# CONTROL.net
KiCad netlist of a schematic drawn in Altium Designer
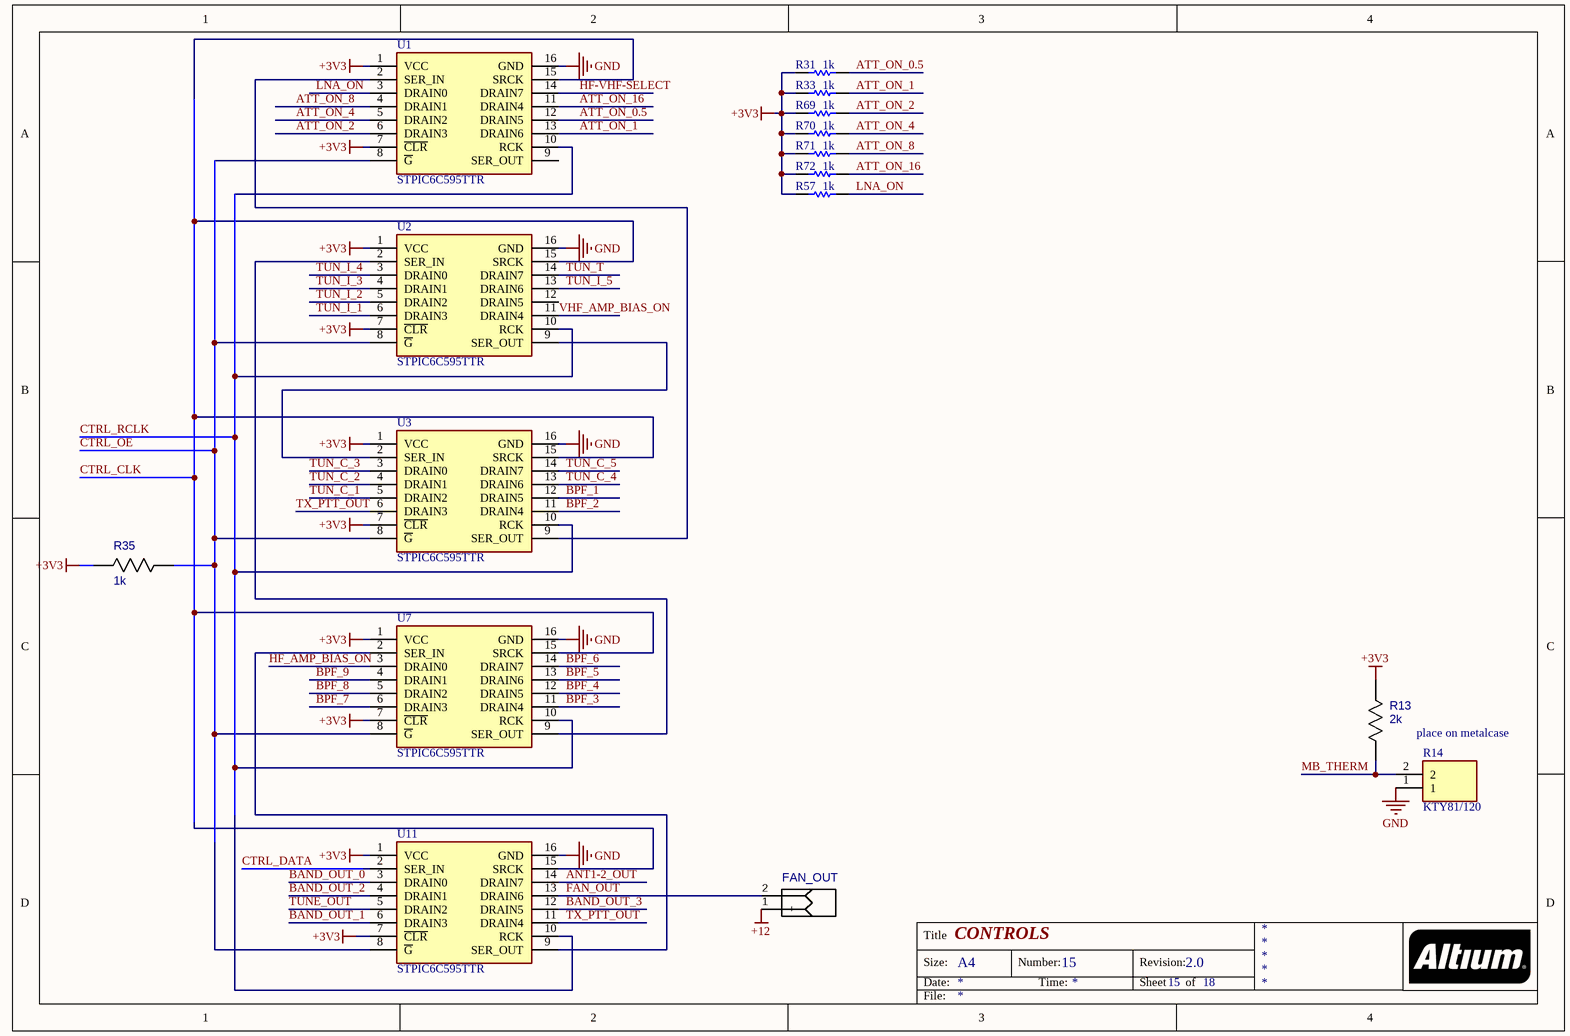
[diagram p0: CONTROL.SchDoc]

(export (version "E")
  (design (tool "Eeschema 10.0.6"))
  (components
    (comp (ref "FAN_OUT")
      (value "51022-0200")
      (footprint "51022-0200")
      (libsource (lib "*") (part "51022-0200"))
    )
    (comp (ref "R13")
      (value "2k")
      (footprint "RES_0805")
      (description "RES_0805")
      (libsource (lib "*") (part "RES_0805"))
    )
    (comp (ref "R14")
      (value "KTY81/120")
      (footprint "TO254P420X460X770-2P")
      (description "Integrated Circuit")
      (fields (field (name "MANUFACTURER_PART_NUMBER") "KTY81/110"))
      (libsource (lib "RF-UNIT-BIG") (part "KTY81_110"))
    )
    (comp (ref "R31")
      (value "1k")
      (footprint "RESC2013X60X40NL20T25")
      (description "RES_0805")
      (fields (field (name "MANUFACTURER") "Panasonic") (field (name "PART NUMBER") "ERA-6AEB303V"))
      (libsource (lib "Altium Content Vault") (part "RES"))
    )
    (comp (ref "R33")
      (value "1k")
      (footprint "RESC2013X60X40NL20T25")
      (description "RES_0805")
      (fields (field (name "MANUFACTURER") "Panasonic") (field (name "PART NUMBER") "ERA-6AEB303V"))
      (libsource (lib "Altium Content Vault") (part "RES"))
    )
    (comp (ref "R35")
      (value "1k")
      (footprint "RES_0805")
      (description "RES_0805")
      (libsource (lib "*") (part "RES_0805"))
    )
    (comp (ref "R57")
      (value "1k")
      (footprint "RESC2013X60X40NL20T25")
      (description "RES_0805")
      (fields (field (name "MANUFACTURER") "Panasonic") (field (name "PART NUMBER") "ERA-6AEB303V"))
      (libsource (lib "Altium Content Vault") (part "RES"))
    )
    (comp (ref "R69")
      (value "1k")
      (footprint "RESC2013X60X40NL20T25")
      (description "RES_0805")
      (fields (field (name "MANUFACTURER") "Panasonic") (field (name "PART NUMBER") "ERA-6AEB303V"))
      (libsource (lib "Altium Content Vault") (part "RES"))
    )
    (comp (ref "R70")
      (value "1k")
      (footprint "RESC2013X60X40NL20T25")
      (description "RES_0805")
      (fields (field (name "MANUFACTURER") "Panasonic") (field (name "PART NUMBER") "ERA-6AEB303V"))
      (libsource (lib "Altium Content Vault") (part "RES"))
    )
    (comp (ref "R71")
      (value "1k")
      (footprint "RESC2013X60X40NL20T25")
      (description "RES_0805")
      (fields (field (name "MANUFACTURER") "Panasonic") (field (name "PART NUMBER") "ERA-6AEB303V"))
      (libsource (lib "Altium Content Vault") (part "RES"))
    )
    (comp (ref "R72")
      (value "1k")
      (footprint "RESC2013X60X40NL20T25")
      (description "RES_0805")
      (fields (field (name "MANUFACTURER") "Panasonic") (field (name "PART NUMBER") "ERA-6AEB303V"))
      (libsource (lib "Altium Content Vault") (part "RES"))
    )
    (comp (ref "U1")
      (value "STPIC6C595TTR")
      (footprint "SamacSys:SOP65P640X120-16N")
      (description "Integrated Circuit")
      (fields (field (name "MOUSER PART NUMBER") "511-STPIC6C595T"))
      (libsource (lib "") (part "STPIC6C595TTR_1"))
    )
    (comp (ref "U2")
      (value "STPIC6C595TTR")
      (footprint "SamacSys:SOP65P640X120-16N")
      (description "Integrated Circuit")
      (fields (field (name "MOUSER PART NUMBER") "511-STPIC6C595T"))
      (libsource (lib "*") (part "STPIC6C595TTR"))
    )
    (comp (ref "U3")
      (value "STPIC6C595TTR")
      (footprint "SamacSys:SOP65P640X120-16N")
      (description "Integrated Circuit")
      (fields (field (name "MOUSER PART NUMBER") "511-STPIC6C595T"))
      (libsource (lib "*") (part "STPIC6C595TTR"))
    )
    (comp (ref "U7")
      (value "STPIC6C595TTR")
      (footprint "SamacSys:SOP65P640X120-16N")
      (description "Integrated Circuit")
      (fields (field (name "MOUSER PART NUMBER") "511-STPIC6C595T"))
      (libsource (lib "*") (part "STPIC6C595TTR"))
    )
    (comp (ref "U11")
      (value "STPIC6C595TTR")
      (footprint "SamacSys:SOP65P640X120-16N")
      (description "Integrated Circuit")
      (fields (field (name "MOUSER PART NUMBER") "511-STPIC6C595T"))
      (libsource (lib "*") (part "STPIC6C595TTR"))
    )
  )
  (nets
    (net (code "1") (name "+3V3") (class "Default")
      (node (ref "R13") (pin "2") (pinfunction "2_2") (pintype "passive"))
      (node (ref "R31") (pin "2") (pinfunction "2_2") (pintype "passive"))
      (node (ref "R33") (pin "2") (pinfunction "2_2") (pintype "passive"))
      (node (ref "R35") (pin "1") (pinfunction "1_1") (pintype "passive"))
      (node (ref "R57") (pin "2") (pinfunction "2_2") (pintype "passive"))
      (node (ref "R69") (pin "2") (pinfunction "2_2") (pintype "passive"))
      (node (ref "R70") (pin "2") (pinfunction "2_2") (pintype "passive"))
      (node (ref "R71") (pin "2") (pinfunction "2_2") (pintype "passive"))
      (node (ref "R72") (pin "2") (pinfunction "2_2") (pintype "passive"))
      (node (ref "U1") (pin "1") (pinfunction "VCC_1") (pintype "passive"))
      (node (ref "U1") (pin "7") (pinfunction "~{CLR}_7") (pintype "passive"))
      (node (ref "U11") (pin "1") (pinfunction "VCC_1") (pintype "passive"))
      (node (ref "U11") (pin "7") (pinfunction "~{CLR}_7") (pintype "passive"))
      (node (ref "U2") (pin "1") (pinfunction "VCC_1") (pintype "passive"))
      (node (ref "U2") (pin "7") (pinfunction "~{CLR}_7") (pintype "passive"))
      (node (ref "U3") (pin "1") (pinfunction "VCC_1") (pintype "passive"))
      (node (ref "U3") (pin "7") (pinfunction "~{CLR}_7") (pintype "passive"))
      (node (ref "U7") (pin "1") (pinfunction "VCC_1") (pintype "passive"))
      (node (ref "U7") (pin "7") (pinfunction "~{CLR}_7") (pintype "passive"))
    )
    (net (code "2") (name "+12") (class "Default")
      (node (ref "FAN_OUT") (pin "1") (pinfunction "+_1") (pintype "passive"))
    )
    (net (code "4") (name "/ANT1-2_OUT") (class "Default")
      (node (ref "U11") (pin "14") (pinfunction "DRAIN7_14") (pintype "passive"))
    )
    (net (code "5") (name "/ATT_ON_0.5") (class "Default")
      (node (ref "R31") (pin "1") (pinfunction "1_1") (pintype "passive"))
      (node (ref "U1") (pin "12") (pinfunction "DRAIN5_12") (pintype "passive"))
    )
    (net (code "6") (name "/ATT_ON_1") (class "Default")
      (node (ref "R33") (pin "1") (pinfunction "1_1") (pintype "passive"))
      (node (ref "U1") (pin "13") (pinfunction "DRAIN6_13") (pintype "passive"))
    )
    (net (code "7") (name "/ATT_ON_2") (class "Default")
      (node (ref "R69") (pin "1") (pinfunction "1_1") (pintype "passive"))
      (node (ref "U1") (pin "6") (pinfunction "DRAIN3_6") (pintype "passive"))
    )
    (net (code "8") (name "/ATT_ON_4") (class "Default")
      (node (ref "R70") (pin "1") (pinfunction "1_1") (pintype "passive"))
      (node (ref "U1") (pin "5") (pinfunction "DRAIN2_5") (pintype "passive"))
    )
    (net (code "9") (name "/ATT_ON_8") (class "Default")
      (node (ref "R71") (pin "1") (pinfunction "1_1") (pintype "passive"))
      (node (ref "U1") (pin "4") (pinfunction "DRAIN1_4") (pintype "passive"))
    )
    (net (code "10") (name "/ATT_ON_16") (class "Default")
      (node (ref "R72") (pin "1") (pinfunction "1_1") (pintype "passive"))
      (node (ref "U1") (pin "11") (pinfunction "DRAIN4_11") (pintype "passive"))
    )
    (net (code "11") (name "/BAND_OUT_0") (class "Default")
      (node (ref "U11") (pin "3") (pinfunction "DRAIN0_3") (pintype "passive"))
    )
    (net (code "12") (name "/BAND_OUT_1") (class "Default")
      (node (ref "U11") (pin "6") (pinfunction "DRAIN3_6") (pintype "passive"))
    )
    (net (code "13") (name "/BAND_OUT_2") (class "Default")
      (node (ref "U11") (pin "4") (pinfunction "DRAIN1_4") (pintype "passive"))
    )
    (net (code "14") (name "/BAND_OUT_3") (class "Default")
      (node (ref "U11") (pin "12") (pinfunction "DRAIN5_12") (pintype "passive"))
    )
    (net (code "15") (name "/BPF_1") (class "Default")
      (node (ref "U3") (pin "12") (pinfunction "DRAIN5_12") (pintype "passive"))
    )
    (net (code "16") (name "/BPF_2") (class "Default")
      (node (ref "U3") (pin "11") (pinfunction "DRAIN4_11") (pintype "passive"))
    )
    (net (code "17") (name "/BPF_3") (class "Default")
      (node (ref "U7") (pin "11") (pinfunction "DRAIN4_11") (pintype "passive"))
    )
    (net (code "18") (name "/BPF_4") (class "Default")
      (node (ref "U7") (pin "12") (pinfunction "DRAIN5_12") (pintype "passive"))
    )
    (net (code "19") (name "/BPF_5") (class "Default")
      (node (ref "U7") (pin "13") (pinfunction "DRAIN6_13") (pintype "passive"))
    )
    (net (code "20") (name "/BPF_6") (class "Default")
      (node (ref "U7") (pin "14") (pinfunction "DRAIN7_14") (pintype "passive"))
    )
    (net (code "21") (name "/BPF_7") (class "Default")
      (node (ref "U7") (pin "6") (pinfunction "DRAIN3_6") (pintype "passive"))
    )
    (net (code "22") (name "/BPF_8") (class "Default")
      (node (ref "U7") (pin "5") (pinfunction "DRAIN2_5") (pintype "passive"))
    )
    (net (code "23") (name "/BPF_9") (class "Default")
      (node (ref "U7") (pin "4") (pinfunction "DRAIN1_4") (pintype "passive"))
    )
    (net (code "24") (name "/CTRL_CLK") (class "Default")
      (node (ref "U1") (pin "15") (pinfunction "SRCK_15") (pintype "passive"))
      (node (ref "U11") (pin "15") (pinfunction "SRCK_15") (pintype "passive"))
      (node (ref "U2") (pin "15") (pinfunction "SRCK_15") (pintype "passive"))
      (node (ref "U3") (pin "15") (pinfunction "SRCK_15") (pintype "passive"))
      (node (ref "U7") (pin "15") (pinfunction "SRCK_15") (pintype "passive"))
    )
    (net (code "25") (name "/CTRL_DATA") (class "Default")
      (node (ref "U11") (pin "2") (pinfunction "SER_IN_2") (pintype "passive"))
    )
    (net (code "26") (name "/CTRL_OE") (class "Default")
      (node (ref "R35") (pin "2") (pinfunction "2_2") (pintype "passive"))
      (node (ref "U1") (pin "8") (pinfunction "~{G}_8") (pintype "passive"))
      (node (ref "U11") (pin "8") (pinfunction "~{G}_8") (pintype "passive"))
      (node (ref "U2") (pin "8") (pinfunction "~{G}_8") (pintype "passive"))
      (node (ref "U3") (pin "8") (pinfunction "~{G}_8") (pintype "passive"))
      (node (ref "U7") (pin "8") (pinfunction "~{G}_8") (pintype "passive"))
    )
    (net (code "27") (name "/CTRL_RCLK") (class "Default")
      (node (ref "U1") (pin "10") (pinfunction "RCK_10") (pintype "passive"))
      (node (ref "U11") (pin "10") (pinfunction "RCK_10") (pintype "passive"))
      (node (ref "U2") (pin "10") (pinfunction "RCK_10") (pintype "passive"))
      (node (ref "U3") (pin "10") (pinfunction "RCK_10") (pintype "passive"))
      (node (ref "U7") (pin "10") (pinfunction "RCK_10") (pintype "passive"))
    )
    (net (code "28") (name "/FAN_OUT") (class "Default")
      (node (ref "FAN_OUT") (pin "2") (pinfunction "-_2") (pintype "passive"))
      (node (ref "U11") (pin "13") (pinfunction "DRAIN6_13") (pintype "passive"))
    )
    (net (code "29") (name "/HF-VHF-SELECT") (class "Default")
      (node (ref "U1") (pin "14") (pinfunction "DRAIN7_14") (pintype "passive"))
    )
    (net (code "30") (name "/HF_AMP_BIAS_ON") (class "Default")
      (node (ref "U7") (pin "3") (pinfunction "DRAIN0_3") (pintype "passive"))
    )
    (net (code "31") (name "/LNA_ON") (class "Default")
      (node (ref "R57") (pin "1") (pinfunction "1_1") (pintype "passive"))
      (node (ref "U1") (pin "3") (pinfunction "DRAIN0_3") (pintype "passive"))
    )
    (net (code "32") (name "/MB_THERM") (class "Default")
      (node (ref "R13") (pin "1") (pinfunction "1_1") (pintype "passive"))
      (node (ref "R14") (pin "2") (pinfunction "2_2") (pintype "passive"))
    )
    (net (code "33") (name "/TUNE_OUT") (class "Default")
      (node (ref "U11") (pin "5") (pinfunction "DRAIN2_5") (pintype "passive"))
    )
    (net (code "34") (name "/TUN_I_1") (class "Default")
      (node (ref "U2") (pin "6") (pinfunction "DRAIN3_6") (pintype "passive"))
    )
    (net (code "35") (name "/TUN_I_2") (class "Default")
      (node (ref "U2") (pin "5") (pinfunction "DRAIN2_5") (pintype "passive"))
    )
    (net (code "36") (name "/TUN_I_3") (class "Default")
      (node (ref "U2") (pin "4") (pinfunction "DRAIN1_4") (pintype "passive"))
    )
    (net (code "37") (name "/TUN_I_4") (class "Default")
      (node (ref "U2") (pin "3") (pinfunction "DRAIN0_3") (pintype "passive"))
    )
    (net (code "38") (name "/TUN_I_5") (class "Default")
      (node (ref "U2") (pin "13") (pinfunction "DRAIN6_13") (pintype "passive"))
    )
    (net (code "39") (name "/TUN_T") (class "Default")
      (node (ref "U2") (pin "14") (pinfunction "DRAIN7_14") (pintype "passive"))
    )
    (net (code "40") (name "/TUN_С_1") (class "Default")
      (node (ref "U3") (pin "5") (pinfunction "DRAIN2_5") (pintype "passive"))
    )
    (net (code "41") (name "/TUN_С_2") (class "Default")
      (node (ref "U3") (pin "4") (pinfunction "DRAIN1_4") (pintype "passive"))
    )
    (net (code "42") (name "/TUN_С_3") (class "Default")
      (node (ref "U3") (pin "3") (pinfunction "DRAIN0_3") (pintype "passive"))
    )
    (net (code "43") (name "/TUN_С_4") (class "Default")
      (node (ref "U3") (pin "13") (pinfunction "DRAIN6_13") (pintype "passive"))
    )
    (net (code "44") (name "/TUN_С_5") (class "Default")
      (node (ref "U3") (pin "14") (pinfunction "DRAIN7_14") (pintype "passive"))
    )
    (net (code "45") (name "/TX_PTT_OUT") (class "Default")
      (node (ref "U11") (pin "11") (pinfunction "DRAIN4_11") (pintype "passive"))
      (node (ref "U3") (pin "6") (pinfunction "DRAIN3_6") (pintype "passive"))
    )
    (net (code "46") (name "/VHF_AMP_BIAS_ON") (class "Default")
      (node (ref "U2") (pin "11") (pinfunction "DRAIN4_11") (pintype "passive"))
    )
    (net (code "47") (name "GND") (class "Default")
      (node (ref "R14") (pin "1") (pinfunction "1_1") (pintype "passive"))
      (node (ref "U1") (pin "16") (pinfunction "GND_16") (pintype "passive"))
      (node (ref "U11") (pin "16") (pinfunction "GND_16") (pintype "passive"))
      (node (ref "U2") (pin "16") (pinfunction "GND_16") (pintype "passive"))
      (node (ref "U3") (pin "16") (pinfunction "GND_16") (pintype "passive"))
      (node (ref "U7") (pin "16") (pinfunction "GND_16") (pintype "passive"))
    )
    (net (code "48") (name "Net-(U1-SER_IN)") (class "Default")
      (node (ref "U1") (pin "2") (pinfunction "SER_IN_2") (pintype "passive"))
      (node (ref "U3") (pin "9") (pinfunction "SER_OUT_9") (pintype "passive"))
    )
    (net (code "49") (name "Net-(U2-SER_IN)") (class "Default")
      (node (ref "U2") (pin "2") (pinfunction "SER_IN_2") (pintype "passive"))
      (node (ref "U7") (pin "9") (pinfunction "SER_OUT_9") (pintype "passive"))
    )
    (net (code "50") (name "Net-(U2-SER_OUT)") (class "Default")
      (node (ref "U2") (pin "9") (pinfunction "SER_OUT_9") (pintype "passive"))
      (node (ref "U3") (pin "2") (pinfunction "SER_IN_2") (pintype "passive"))
    )
    (net (code "51") (name "Net-(U11-SER_OUT)") (class "Default")
      (node (ref "U11") (pin "9") (pinfunction "SER_OUT_9") (pintype "passive"))
      (node (ref "U7") (pin "2") (pinfunction "SER_IN_2") (pintype "passive"))
    )
    (net (code "52") (name "unconnected-(U1-SER_OUT-Pad9)") (class "Default")
      (node (ref "U1") (pin "9") (pinfunction "SER_OUT_9") (pintype "passive"))
    )
    (net (code "53") (name "unconnected-(U2-DRAIN5-Pad12)") (class "Default")
      (node (ref "U2") (pin "12") (pinfunction "DRAIN5_12") (pintype "passive"))
    )
  )
)
